# 501_GridPos5.net
KiCad netlist of a schematic drawn in Altium Designer
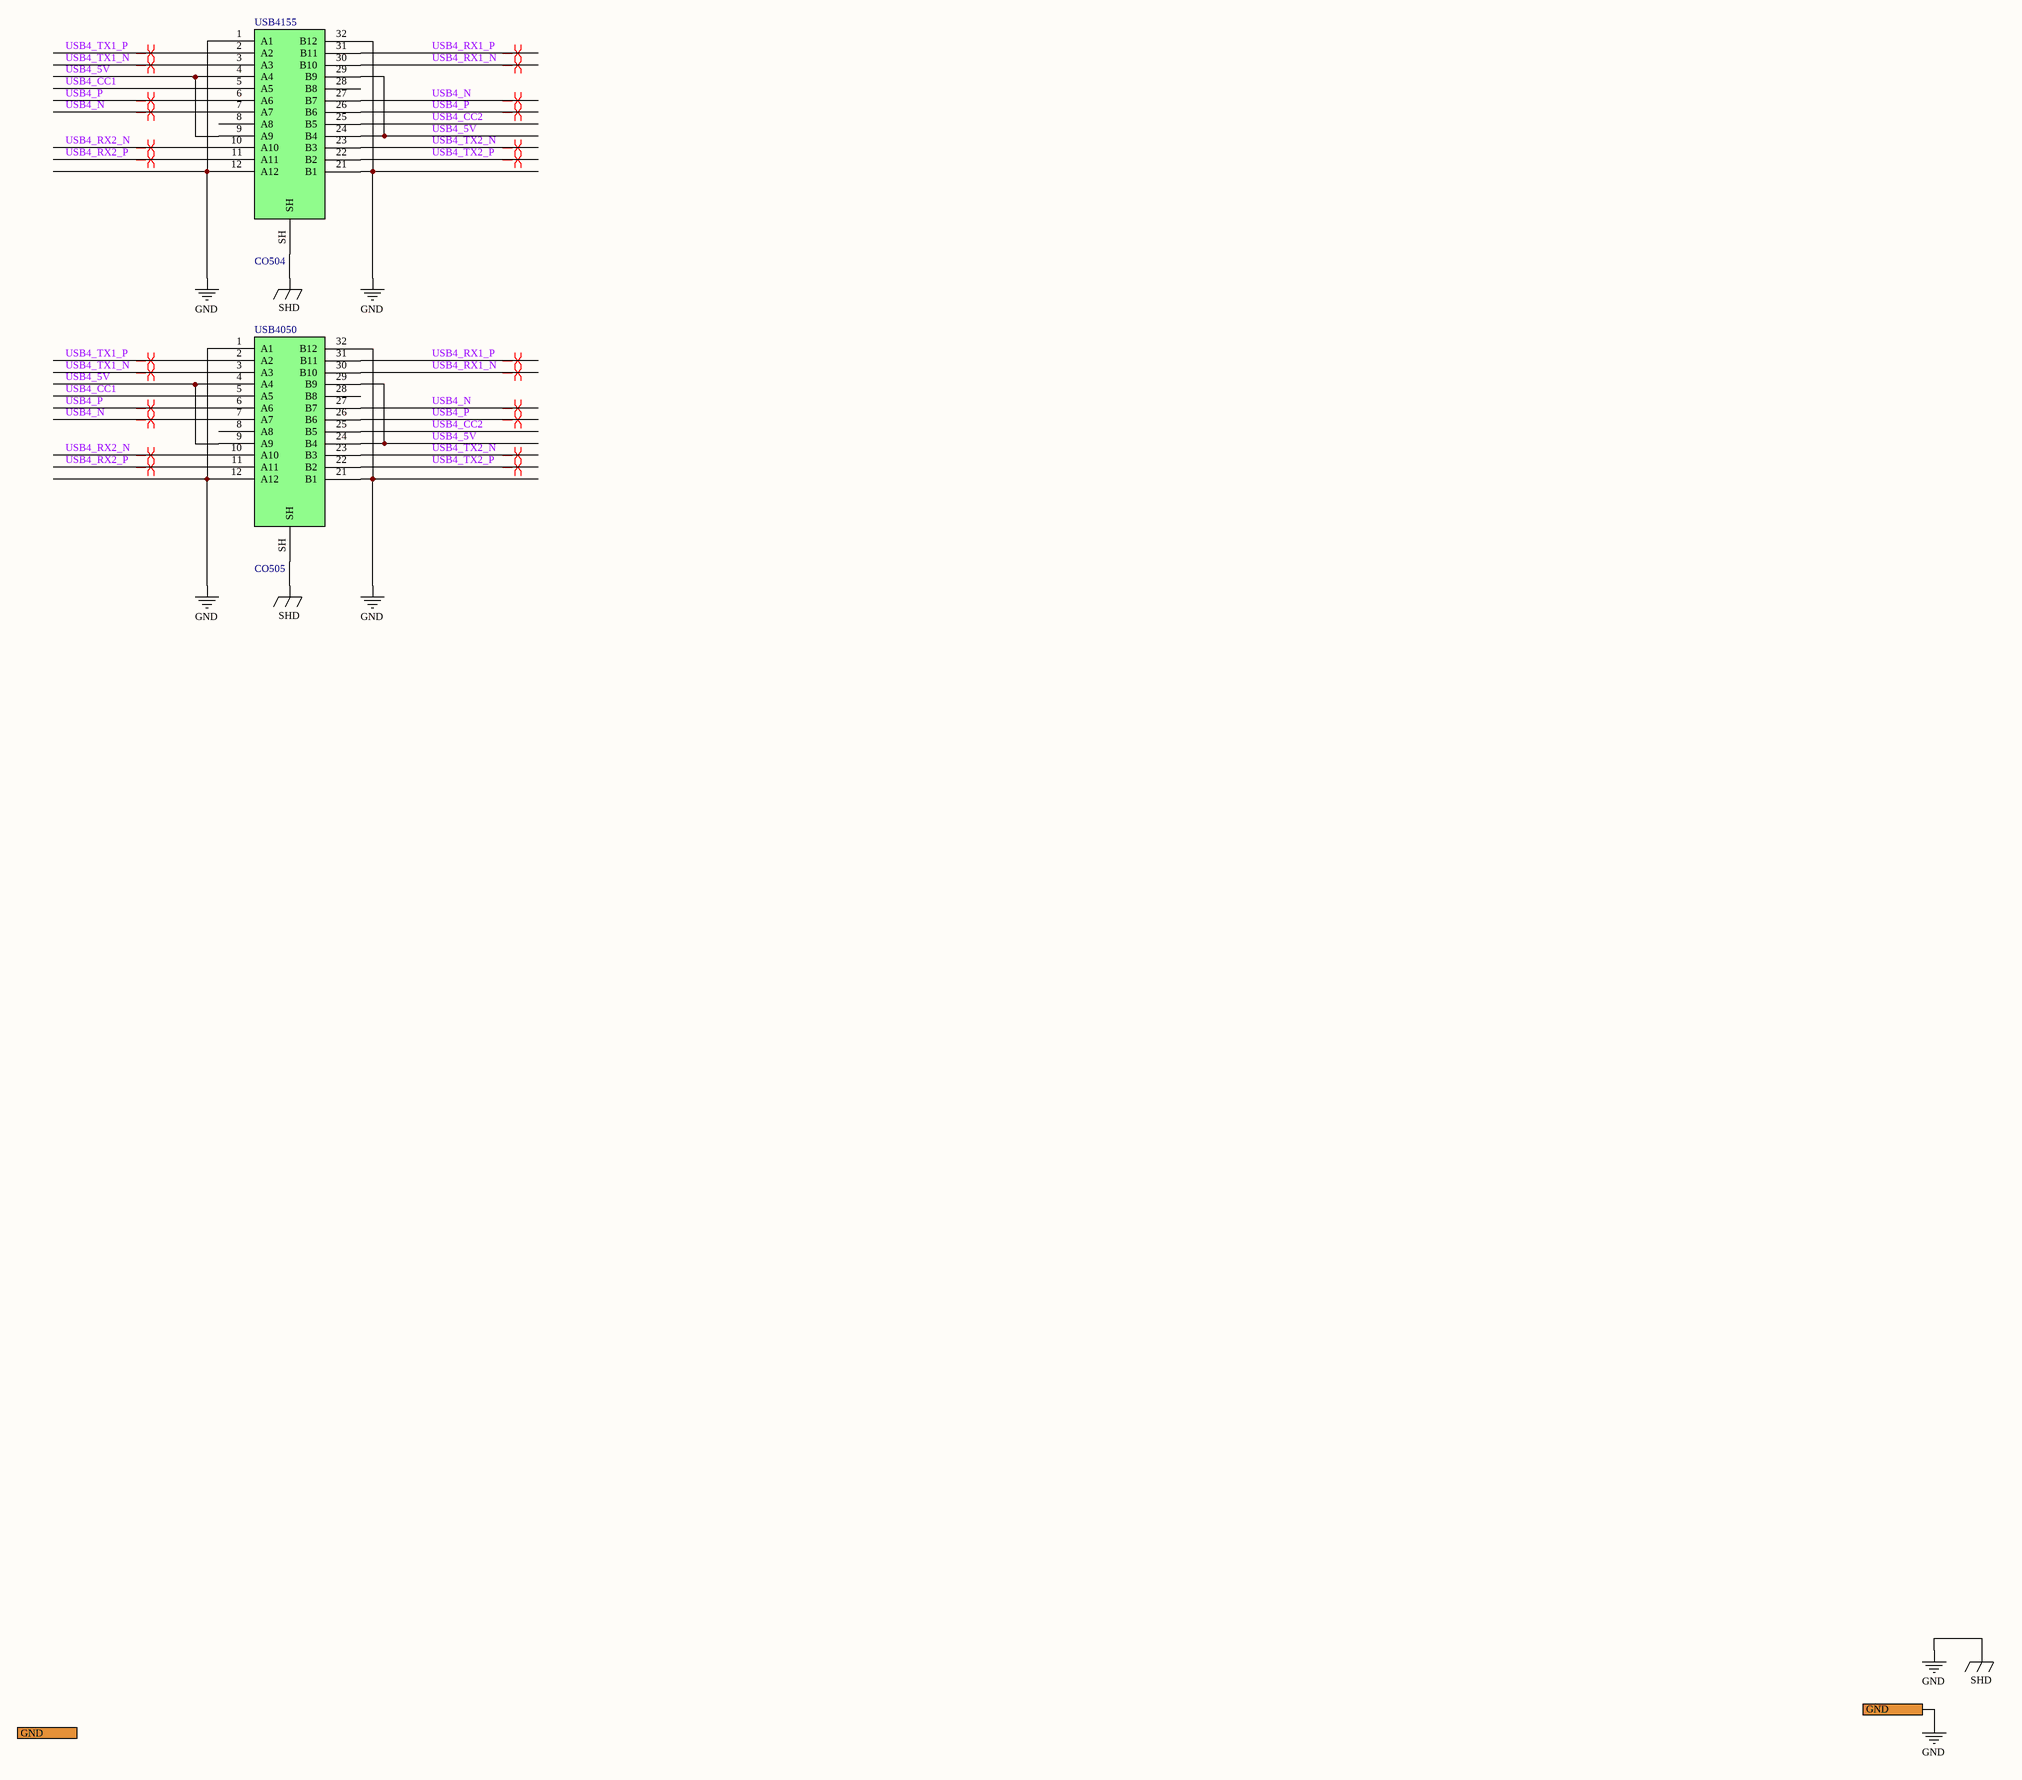
[diagram p0: 501_GridPos5.SchDoc]

(export (version "E")
  (design (tool "Eeschema 10.0.6"))
  (components
    (comp (ref "CO504")
      (value "USB4155")
      (footprint "USB4155-03-C")
      (description "USB C connector Plug Horizontal")
      (fields
        (field (name "REFVAL") "USB4155")
        (field (name "PART NUMBER") "CO0031")
        (field (name "MANFACTPART") "USB4155-03-C")
      )
      (libsource (lib "GTS_Database") (part "USB-CC"))
    )
    (comp (ref "CO505")
      (value "USB4050")
      (footprint "USB4050-30-A")
      (description "USB C connector Receptacle Horizontal")
      (fields
        (field (name "REFVAL") "USB4050")
        (field (name "PART NUMBER") "CO0039")
        (field (name "MANFACTPART") "USB4050-30-A")
      )
      (libsource (lib "GTS_Database") (part "USB-CC"))
    )
  )
  (nets
    (net (code "1") (name "/USB4_5V") (class "Default")
      (node (ref "CO504") (pin "24") (pinfunction "B4_24") (pintype "passive"))
      (node (ref "CO504") (pin "29") (pinfunction "B9_29") (pintype "passive"))
      (node (ref "CO504") (pin "4") (pinfunction "A4_4") (pintype "passive"))
      (node (ref "CO504") (pin "9") (pinfunction "A9_9") (pintype "passive"))
      (node (ref "CO505") (pin "24") (pinfunction "B4_24") (pintype "passive"))
      (node (ref "CO505") (pin "29") (pinfunction "B9_29") (pintype "passive"))
      (node (ref "CO505") (pin "4") (pinfunction "A4_4") (pintype "passive"))
      (node (ref "CO505") (pin "9") (pinfunction "A9_9") (pintype "passive"))
    )
    (net (code "2") (name "/USB4_CC1") (class "Default")
      (node (ref "CO504") (pin "5") (pinfunction "A5_5") (pintype "passive"))
      (node (ref "CO505") (pin "5") (pinfunction "A5_5") (pintype "passive"))
    )
    (net (code "3") (name "/USB4_CC2") (class "Default")
      (node (ref "CO504") (pin "25") (pinfunction "B5_25") (pintype "passive"))
      (node (ref "CO505") (pin "25") (pinfunction "B5_25") (pintype "passive"))
    )
    (net (code "4") (name "/USB4_N") (class "Default")
      (node (ref "CO504") (pin "27") (pinfunction "B7_27") (pintype "passive"))
      (node (ref "CO504") (pin "7") (pinfunction "A7_7") (pintype "passive"))
      (node (ref "CO505") (pin "27") (pinfunction "B7_27") (pintype "passive"))
      (node (ref "CO505") (pin "7") (pinfunction "A7_7") (pintype "passive"))
    )
    (net (code "5") (name "/USB4_P") (class "Default")
      (node (ref "CO504") (pin "26") (pinfunction "B6_26") (pintype "passive"))
      (node (ref "CO504") (pin "6") (pinfunction "A6_6") (pintype "passive"))
      (node (ref "CO505") (pin "26") (pinfunction "B6_26") (pintype "passive"))
      (node (ref "CO505") (pin "6") (pinfunction "A6_6") (pintype "passive"))
    )
    (net (code "6") (name "/USB4_RX1_N") (class "Default")
      (node (ref "CO504") (pin "30") (pinfunction "B10_30") (pintype "passive"))
      (node (ref "CO505") (pin "30") (pinfunction "B10_30") (pintype "passive"))
    )
    (net (code "7") (name "/USB4_RX1_P") (class "Default")
      (node (ref "CO504") (pin "31") (pinfunction "B11_31") (pintype "passive"))
      (node (ref "CO505") (pin "31") (pinfunction "B11_31") (pintype "passive"))
    )
    (net (code "8") (name "/USB4_RX2_N") (class "Default")
      (node (ref "CO504") (pin "10") (pinfunction "A10_10") (pintype "passive"))
      (node (ref "CO505") (pin "10") (pinfunction "A10_10") (pintype "passive"))
    )
    (net (code "9") (name "/USB4_RX2_P") (class "Default")
      (node (ref "CO504") (pin "11") (pinfunction "A11_11") (pintype "passive"))
      (node (ref "CO505") (pin "11") (pinfunction "A11_11") (pintype "passive"))
    )
    (net (code "10") (name "/USB4_TX1_N") (class "Default")
      (node (ref "CO504") (pin "3") (pinfunction "A3_3") (pintype "passive"))
      (node (ref "CO505") (pin "3") (pinfunction "A3_3") (pintype "passive"))
    )
    (net (code "11") (name "/USB4_TX1_P") (class "Default")
      (node (ref "CO504") (pin "2") (pinfunction "A2_2") (pintype "passive"))
      (node (ref "CO505") (pin "2") (pinfunction "A2_2") (pintype "passive"))
    )
    (net (code "12") (name "/USB4_TX2_N") (class "Default")
      (node (ref "CO504") (pin "23") (pinfunction "B3_23") (pintype "passive"))
      (node (ref "CO505") (pin "23") (pinfunction "B3_23") (pintype "passive"))
    )
    (net (code "13") (name "/USB4_TX2_P") (class "Default")
      (node (ref "CO504") (pin "22") (pinfunction "B2_22") (pintype "passive"))
      (node (ref "CO505") (pin "22") (pinfunction "B2_22") (pintype "passive"))
    )
    (net (code "14") (name "GND") (class "Default")
      (node (ref "CO504") (pin "1") (pinfunction "A1_1") (pintype "passive"))
      (node (ref "CO504") (pin "12") (pinfunction "A12_12") (pintype "passive"))
      (node (ref "CO504") (pin "21") (pinfunction "B1_21") (pintype "passive"))
      (node (ref "CO504") (pin "32") (pinfunction "B12_32") (pintype "passive"))
      (node (ref "CO504") (pin "SH") (pinfunction "SH_SH") (pintype "power_in"))
      (node (ref "CO505") (pin "1") (pinfunction "A1_1") (pintype "passive"))
      (node (ref "CO505") (pin "12") (pinfunction "A12_12") (pintype "passive"))
      (node (ref "CO505") (pin "21") (pinfunction "B1_21") (pintype "passive"))
      (node (ref "CO505") (pin "32") (pinfunction "B12_32") (pintype "passive"))
      (node (ref "CO505") (pin "SH") (pinfunction "SH_SH") (pintype "power_in"))
    )
    (net (code "15") (name "unconnected-(CO504-A8-Pad8)") (class "Default")
      (node (ref "CO504") (pin "8") (pinfunction "A8_8") (pintype "passive"))
    )
    (net (code "16") (name "unconnected-(CO504-B8-Pad28)") (class "Default")
      (node (ref "CO504") (pin "28") (pinfunction "B8_28") (pintype "passive"))
    )
    (net (code "17") (name "unconnected-(CO505-A8-Pad8)") (class "Default")
      (node (ref "CO505") (pin "8") (pinfunction "A8_8") (pintype "passive"))
    )
    (net (code "18") (name "unconnected-(CO505-B8-Pad28)") (class "Default")
      (node (ref "CO505") (pin "28") (pinfunction "B8_28") (pintype "passive"))
    )
  )
)
